# Current_sensors.net
KiCad netlist of a schematic drawn in Altium Designer
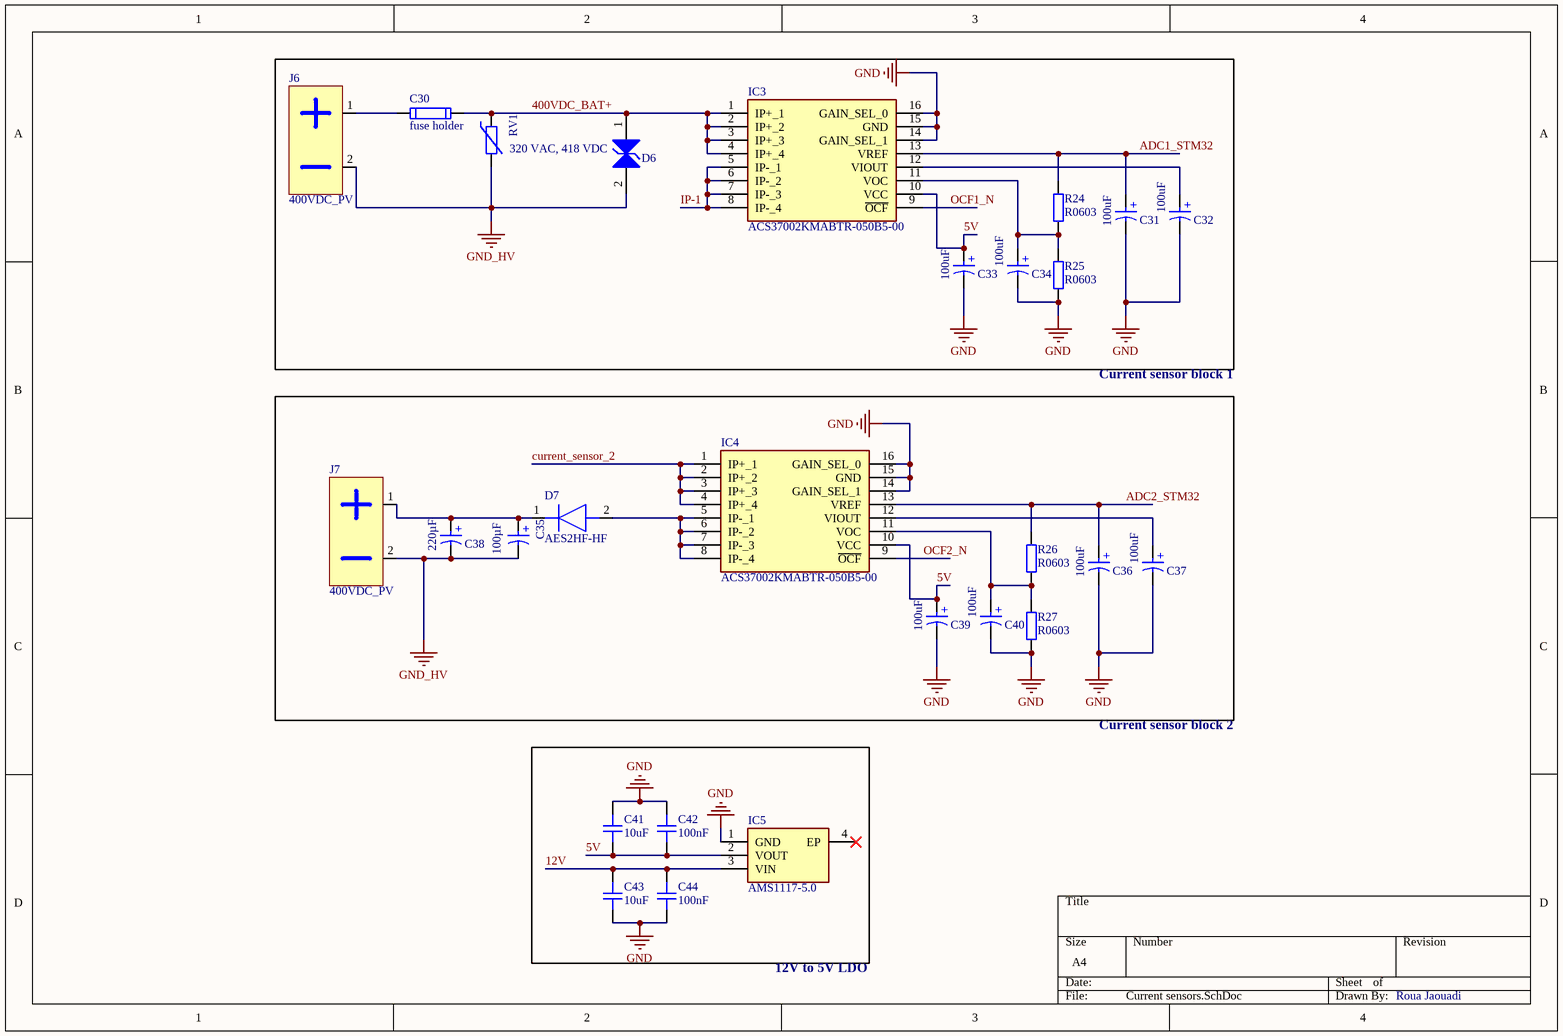
[diagram p0: Current sensors.SchDoc]

(export (version "E")
  (design (tool "Eeschema 10.0.6"))
  (components
    (comp (ref "C30")
      (value "fuse holder")
      (footprint "696108003002")
      (description "FUSEHOLDER BLOCKS - PCB - CLIP COVER - THT - WR-FSH")
      (fields
        (field (name "MANUFACTURER") "Würth Elektronik eiSos GmbH")
        (field (name "PARTNO") "696108003002")
        (field (name "CREATED BY") "Karrer Zheng")
      )
      (libsource (lib "Fuse Holder Connectors") (part "WE-FUSEHOLDER BLOCKS 696108003002"))
    )
    (comp (ref "C31")
      (value "100uF")
      (footprint "WCAP-ATG8_D5H11")
      (description "WCAP-ATG8 Aluminum Electrolytic Capacitor, Radial, THT, D5 x H11mm, 100uF, 10V")
      (fields
        (field (name "MANUFACTURER PART NUMBER") "860010272005")
        (field (name "MANUFACTURER") "Wurth Elektronik")
      )
      (libsource (lib "Schlib1") (part "860010272005"))
    )
    (comp (ref "C32")
      (value "100uF")
      (footprint "WCAP-ATG8_D5H11")
      (description "WCAP-ATG8 Aluminum Electrolytic Capacitor, Radial, THT, D5 x H11mm, 100uF, 10V")
      (fields
        (field (name "MANUFACTURER PART NUMBER") "860010272005")
        (field (name "MANUFACTURER") "Wurth Elektronik")
      )
      (libsource (lib "Schlib1") (part "860010272005"))
    )
    (comp (ref "C33")
      (value "100uF")
      (footprint "WCAP-ATG8_D5H11")
      (description "WCAP-ATG8 Aluminum Electrolytic Capacitor, Radial, THT, D5 x H11mm, 100uF, 10V")
      (fields
        (field (name "MANUFACTURER PART NUMBER") "860010272005")
        (field (name "MANUFACTURER") "Wurth Elektronik")
      )
      (libsource (lib "Schlib1") (part "860010272005"))
    )
    (comp (ref "C34")
      (value "100uF")
      (footprint "WCAP-ATG8_D5H11")
      (description "WCAP-ATG8 Aluminum Electrolytic Capacitor, Radial, THT, D5 x H11mm, 100uF, 10V")
      (fields
        (field (name "MANUFACTURER PART NUMBER") "860010272005")
        (field (name "MANUFACTURER") "Wurth Elektronik")
      )
      (libsource (lib "Schlib1") (part "860010272005"))
    )
    (comp (ref "C35")
      (value "100µF")
      (footprint "WCAP-AT1H:WCAP-AT1H_D16H35.5")
      (description "WCAP-AT1H Aluminum Electrolytic Capacitor, Radial, D16 x H35.5mm, 100µF, 450V")
      (fields
        (field (name "MANUFACTURER PART NUMBER") "860241480001")
        (field (name "MANUFACTURER") "Wurth Elektronik")
      )
      (libsource (lib "WCAP-AT1H") (part "860241480001"))
    )
    (comp (ref "C36")
      (value "100uF")
      (footprint "WCAP-ATG8_D5H11")
      (description "WCAP-ATG8 Aluminum Electrolytic Capacitor, Radial, THT, D5 x H11mm, 100uF, 10V")
      (fields
        (field (name "MANUFACTURER PART NUMBER") "860010272005")
        (field (name "MANUFACTURER") "Wurth Elektronik")
      )
      (libsource (lib "Schlib1") (part "860010272005"))
    )
    (comp (ref "C37")
      (value "100uF")
      (footprint "WCAP-ATG8_D5H11")
      (description "WCAP-ATG8 Aluminum Electrolytic Capacitor, Radial, THT, D5 x H11mm, 100uF, 10V")
      (fields
        (field (name "MANUFACTURER PART NUMBER") "860010272005")
        (field (name "MANUFACTURER") "Wurth Elektronik")
      )
      (libsource (lib "Schlib1") (part "860010272005"))
    )
    (comp (ref "C38")
      (value "220µF")
      (footprint "WCAP-AIE8:WCAP-AIE8_D25H40")
      (description "WCAP-AIE8 Aluminum Electrolytic Capacitor, Snap-In, D25 x H40mm, 220µF, 450V")
      (fields
        (field (name "MANUFACTURER PART NUMBER") "861221484011")
        (field (name "MANUFACTURER") "Wurth Elektronik")
      )
      (libsource (lib "WCAP-AIE8") (part "861221484011"))
    )
    (comp (ref "C39")
      (value "100uF")
      (footprint "WCAP-ATG8_D5H11")
      (description "WCAP-ATG8 Aluminum Electrolytic Capacitor, Radial, THT, D5 x H11mm, 100uF, 10V")
      (fields
        (field (name "MANUFACTURER PART NUMBER") "860010272005")
        (field (name "MANUFACTURER") "Wurth Elektronik")
      )
      (libsource (lib "Schlib1") (part "860010272005"))
    )
    (comp (ref "C40")
      (value "100uF")
      (footprint "WCAP-ATG8_D5H11")
      (description "WCAP-ATG8 Aluminum Electrolytic Capacitor, Radial, THT, D5 x H11mm, 100uF, 10V")
      (fields
        (field (name "MANUFACTURER PART NUMBER") "860010272005")
        (field (name "MANUFACTURER") "Wurth Elektronik")
      )
      (libsource (lib "Schlib1") (part "860010272005"))
    )
    (comp (ref "C41")
      (value "10uF")
      (footprint "CAP_0603")
      (description "Capacitor SMD 0603")
      (libsource (lib "Schematic-Lib-PhilsLab") (part "CAP_0603"))
    )
    (comp (ref "C42")
      (value "100nF")
      (footprint "CAP_0603")
      (description "Capacitor SMD 0603")
      (libsource (lib "Schematic-Lib-PhilsLab") (part "CAP_0603"))
    )
    (comp (ref "C43")
      (value "10uF")
      (footprint "CAP_0603")
      (description "Capacitor SMD 0603")
      (libsource (lib "Schematic-Lib-PhilsLab") (part "CAP_0603"))
    )
    (comp (ref "C44")
      (value "100nF")
      (footprint "CAP_0603")
      (description "Capacitor SMD 0603")
      (libsource (lib "Schematic-Lib-PhilsLab") (part "CAP_0603"))
    )
    (comp (ref "D6")
      (value "600W, 5VDC")
      (footprint "WE-TVSP:WE-TVSP_DO-214AA_Bidirectional")
      (description "WE-TVSP SMT Power TVS Diode, DO-214AA, Bidirectional, 600W, 5VDC")
      (fields
        (field (name "MANUFACTURER PART NUMBER") "824521500")
        (field (name "MANUFACTURER") "Wurth Elektronik")
      )
      (libsource (lib "WE-TVSP") (part "824521500"))
    )
    (comp (ref "D7")
      (value "AES2HF-HF")
      (footprint "SamacSys:SODFL5226X110N")
      (description "Diode")
      (fields (field (name "MOUSER PART NUMBER") "750-AES2HF-HF"))
      (libsource (lib "*") (part "AES2HF-HF"))
    )
    (comp (ref "IC3")
      (value "ACS37002KMABTR-050B5-00")
      (footprint "SamacSys:SOIC127P1030X265-16N")
      (description "Integrated Circuit")
      (libsource (lib "*") (part "ACS37002KMABTR-050B5-00"))
    )
    (comp (ref "IC4")
      (value "ACS37002KMABTR-050B5-00")
      (footprint "SamacSys:SOIC127P1030X265-16N")
      (description "Integrated Circuit")
      (libsource (lib "*") (part "ACS37002KMABTR-050B5-00"))
    )
    (comp (ref "IC5")
      (value "AMS1117-5.0")
      (footprint "SamacSys:SOT290P700X180-4N")
      (description "Integrated Circuit")
      (libsource (lib "*") (part "AMS1117-5.0"))
    )
    (comp (ref "J6")
      (value "400VDC_PV")
      (footprint "XT60PW-F")
      (description "XT60 horizontal female 2-pin AMASS")
      (fields (field (name "MANUFACTURER") "AMASS") (field (name "MANUFACTURER PART NUMBER") "XT60PW-F"))
      (libsource (lib "Schlib1") (part "XT60PW-F"))
    )
    (comp (ref "J7")
      (value "400VDC_PV")
      (footprint "XT60PW-F")
      (description "XT60 horizontal female 2-pin AMASS")
      (fields (field (name "MANUFACTURER") "AMASS") (field (name "MANUFACTURER PART NUMBER") "XT60PW-F"))
      (libsource (lib "Schlib1") (part "XT60PW-F"))
    )
    (comp (ref "R24")
      (value "R0603")
      (footprint "RES_0603")
      (description "Resistor SMD 0603")
      (libsource (lib "Schlib1") (part "RES_0603"))
    )
    (comp (ref "R25")
      (value "R0603")
      (footprint "RES_0603")
      (description "Resistor SMD 0603")
      (libsource (lib "Schlib1") (part "RES_0603"))
    )
    (comp (ref "R26")
      (value "R0603")
      (footprint "RES_0603")
      (description "Resistor SMD 0603")
      (libsource (lib "Schlib1") (part "RES_0603"))
    )
    (comp (ref "R27")
      (value "R0603")
      (footprint "RES_0603")
      (description "Resistor SMD 0603")
      (libsource (lib "Schlib1") (part "RES_0603"))
    )
    (comp (ref "RV1")
      (value "320 VAC, 418 VDC")
      (footprint "D16.5W7.2H20.5P1.6")
      (description "WE-VD Disk Varistor, D16.5 x H20.5 mm, 320 VAC, 418 VDC")
      (fields
        (field (name "MANUFACTURER PART NUMBER") "820443211E")
        (field (name "MANUFACTURER") "Wurth Elektronik")
      )
      (libsource (lib "Schlib1") (part "820443211E"))
    )
  )
  (nets
    (net (code "1") (name "/5V") (class "Default")
      (node (ref "C33") (pin "1") (pinfunction "P_1") (pintype "passive"))
      (node (ref "C39") (pin "1") (pinfunction "P_1") (pintype "passive"))
      (node (ref "C41") (pin "2") (pinfunction "2_2") (pintype "passive"))
      (node (ref "C42") (pin "2") (pinfunction "2_2") (pintype "passive"))
      (node (ref "IC3") (pin "10") (pinfunction "VCC_10") (pintype "passive"))
      (node (ref "IC4") (pin "10") (pinfunction "VCC_10") (pintype "passive"))
      (node (ref "IC5") (pin "2") (pinfunction "VOUT_2") (pintype "passive"))
    )
    (net (code "2") (name "/12V") (class "Default")
      (node (ref "C43") (pin "1") (pinfunction "1_1") (pintype "passive"))
      (node (ref "C44") (pin "1") (pinfunction "1_1") (pintype "passive"))
      (node (ref "IC5") (pin "3") (pinfunction "VIN_3") (pintype "passive"))
    )
    (net (code "3") (name "/400VDC_BAT+") (class "Default")
      (node (ref "C30") (pin "2") (pinfunction "2_2") (pintype "passive"))
      (node (ref "D6") (pin "1") (pinfunction "1_1") (pintype "passive"))
      (node (ref "IC3") (pin "1") (pinfunction "IP+_1_1") (pintype "passive"))
      (node (ref "IC3") (pin "2") (pinfunction "IP+_2_2") (pintype "passive"))
      (node (ref "IC3") (pin "3") (pinfunction "IP+_3_3") (pintype "passive"))
      (node (ref "IC3") (pin "4") (pinfunction "IP+_4_4") (pintype "passive"))
      (node (ref "RV1") (pin "1") (pinfunction "1_1") (pintype "passive"))
    )
    (net (code "4") (name "/ADC1_STM32") (class "Default")
      (node (ref "C31") (pin "1") (pinfunction "P_1") (pintype "passive"))
      (node (ref "IC3") (pin "13") (pinfunction "VREF_13") (pintype "passive"))
      (node (ref "R24") (pin "1") (pinfunction "1_1") (pintype "passive"))
    )
    (net (code "5") (name "/ADC2_STM32") (class "Default")
      (node (ref "C36") (pin "1") (pinfunction "P_1") (pintype "passive"))
      (node (ref "IC4") (pin "13") (pinfunction "VREF_13") (pintype "passive"))
      (node (ref "R26") (pin "1") (pinfunction "1_1") (pintype "passive"))
    )
    (net (code "6") (name "/IP-1") (class "Default")
      (node (ref "IC3") (pin "5") (pinfunction "IP-_1_5") (pintype "passive"))
      (node (ref "IC3") (pin "6") (pinfunction "IP-_2_6") (pintype "passive"))
      (node (ref "IC3") (pin "7") (pinfunction "IP-_3_7") (pintype "passive"))
      (node (ref "IC3") (pin "8") (pinfunction "IP-_4_8") (pintype "passive"))
    )
    (net (code "7") (name "/OCF1_N") (class "Default")
      (node (ref "IC3") (pin "9") (pinfunction "~{OCF}_9") (pintype "passive"))
    )
    (net (code "8") (name "/OCF2_N") (class "Default")
      (node (ref "IC4") (pin "9") (pinfunction "~{OCF}_9") (pintype "passive"))
    )
    (net (code "9") (name "/current_sensor_2") (class "Default")
      (node (ref "IC4") (pin "1") (pinfunction "IP+_1_1") (pintype "passive"))
      (node (ref "IC4") (pin "2") (pinfunction "IP+_2_2") (pintype "passive"))
      (node (ref "IC4") (pin "3") (pinfunction "IP+_3_3") (pintype "passive"))
      (node (ref "IC4") (pin "4") (pinfunction "IP+_4_4") (pintype "passive"))
    )
    (net (code "10") (name "GND") (class "Default")
      (node (ref "C31") (pin "2") (pinfunction "N_2") (pintype "passive"))
      (node (ref "C32") (pin "2") (pinfunction "N_2") (pintype "passive"))
      (node (ref "C33") (pin "2") (pinfunction "N_2") (pintype "passive"))
      (node (ref "C34") (pin "2") (pinfunction "N_2") (pintype "passive"))
      (node (ref "C36") (pin "2") (pinfunction "N_2") (pintype "passive"))
      (node (ref "C37") (pin "2") (pinfunction "N_2") (pintype "passive"))
      (node (ref "C39") (pin "2") (pinfunction "N_2") (pintype "passive"))
      (node (ref "C40") (pin "2") (pinfunction "N_2") (pintype "passive"))
      (node (ref "C41") (pin "1") (pinfunction "1_1") (pintype "passive"))
      (node (ref "C42") (pin "1") (pinfunction "1_1") (pintype "passive"))
      (node (ref "C43") (pin "2") (pinfunction "2_2") (pintype "passive"))
      (node (ref "C44") (pin "2") (pinfunction "2_2") (pintype "passive"))
      (node (ref "IC3") (pin "14") (pinfunction "GAIN_SEL_1_14") (pintype "passive"))
      (node (ref "IC3") (pin "15") (pinfunction "GND_15") (pintype "passive"))
      (node (ref "IC3") (pin "16") (pinfunction "GAIN_SEL_0_16") (pintype "passive"))
      (node (ref "IC4") (pin "14") (pinfunction "GAIN_SEL_1_14") (pintype "passive"))
      (node (ref "IC4") (pin "15") (pinfunction "GND_15") (pintype "passive"))
      (node (ref "IC4") (pin "16") (pinfunction "GAIN_SEL_0_16") (pintype "passive"))
      (node (ref "IC5") (pin "1") (pinfunction "GND_1") (pintype "passive"))
      (node (ref "R25") (pin "2") (pinfunction "2_2") (pintype "passive"))
      (node (ref "R27") (pin "2") (pinfunction "2_2") (pintype "passive"))
    )
    (net (code "11") (name "GND_HV") (class "Default")
      (node (ref "C35") (pin "2") (pinfunction "N_2") (pintype "passive"))
      (node (ref "C38") (pin "2") (pinfunction "N_2") (pintype "passive"))
      (node (ref "D6") (pin "2") (pinfunction "2_2") (pintype "passive"))
      (node (ref "J6") (pin "2") (pinfunction "V-_2") (pintype "power_in"))
      (node (ref "J7") (pin "2") (pinfunction "V-_2") (pintype "power_in"))
      (node (ref "RV1") (pin "2") (pinfunction "2_2") (pintype "passive"))
    )
    (net (code "12") (name "Net-(C32-P)") (class "Default")
      (node (ref "C32") (pin "1") (pinfunction "P_1") (pintype "passive"))
      (node (ref "IC3") (pin "12") (pinfunction "VIOUT_12") (pintype "passive"))
    )
    (net (code "13") (name "Net-(C34-P)") (class "Default")
      (node (ref "C34") (pin "1") (pinfunction "P_1") (pintype "passive"))
      (node (ref "IC3") (pin "11") (pinfunction "VOC_11") (pintype "passive"))
      (node (ref "R24") (pin "2") (pinfunction "2_2") (pintype "passive"))
      (node (ref "R25") (pin "1") (pinfunction "1_1") (pintype "passive"))
    )
    (net (code "14") (name "Net-(C35-P)") (class "Default")
      (node (ref "C35") (pin "1") (pinfunction "P_1") (pintype "passive"))
      (node (ref "C38") (pin "1") (pinfunction "P_1") (pintype "passive"))
      (node (ref "D7") (pin "1") (pinfunction "K_1") (pintype "passive"))
      (node (ref "J7") (pin "1") (pinfunction "V+_1") (pintype "power_in"))
    )
    (net (code "15") (name "Net-(C37-P)") (class "Default")
      (node (ref "C37") (pin "1") (pinfunction "P_1") (pintype "passive"))
      (node (ref "IC4") (pin "12") (pinfunction "VIOUT_12") (pintype "passive"))
    )
    (net (code "16") (name "Net-(C40-P)") (class "Default")
      (node (ref "C40") (pin "1") (pinfunction "P_1") (pintype "passive"))
      (node (ref "IC4") (pin "11") (pinfunction "VOC_11") (pintype "passive"))
      (node (ref "R26") (pin "2") (pinfunction "2_2") (pintype "passive"))
      (node (ref "R27") (pin "1") (pinfunction "1_1") (pintype "passive"))
    )
    (net (code "17") (name "Net-(D7-A)") (class "Default")
      (node (ref "D7") (pin "2") (pinfunction "A_2") (pintype "passive"))
      (node (ref "IC4") (pin "5") (pinfunction "IP-_1_5") (pintype "passive"))
      (node (ref "IC4") (pin "6") (pinfunction "IP-_2_6") (pintype "passive"))
      (node (ref "IC4") (pin "7") (pinfunction "IP-_3_7") (pintype "passive"))
      (node (ref "IC4") (pin "8") (pinfunction "IP-_4_8") (pintype "passive"))
    )
    (net (code "18") (name "Net-(J6-V+)") (class "Default")
      (node (ref "C30") (pin "1") (pinfunction "1_1") (pintype "passive"))
      (node (ref "J6") (pin "1") (pinfunction "V+_1") (pintype "power_in"))
    )
    (net (code "19") (name "unconnected-(IC5-EP-Pad4)") (class "Default")
      (node (ref "IC5") (pin "4") (pinfunction "EP_4") (pintype "passive+no_connect"))
    )
  )
)
